# Touch_Cat_0_6.net
KiCad netlist of a schematic drawn in EAGLE
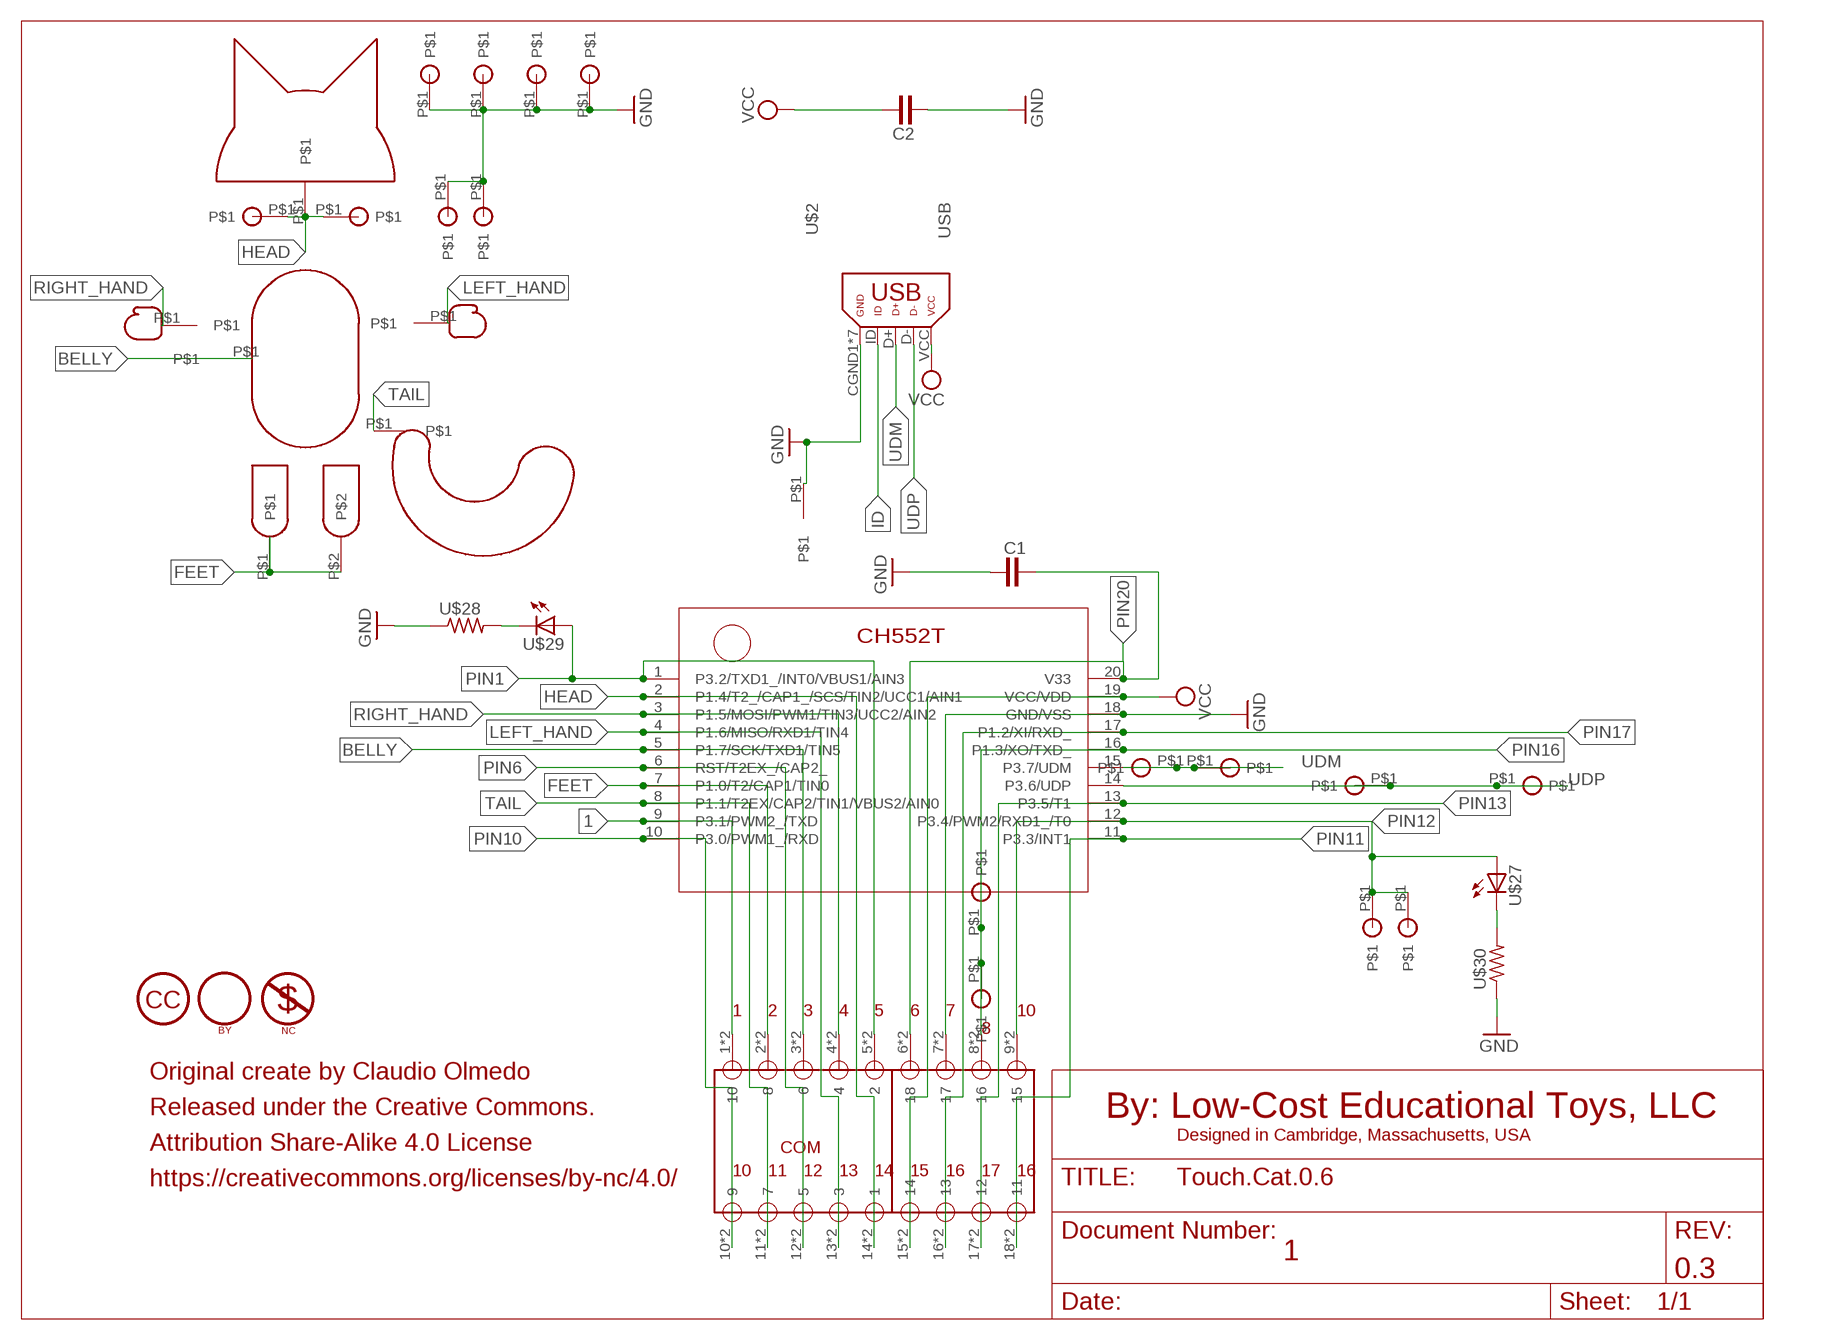
[diagram p0: schematic, sheet 1]

(export (version "E")
  (design (tool "Eeschema 10.0.6"))
  (components
    (comp (ref "C1")
      (value "CAPACITOR")
      (footprint "eagle-import:C0402")
      (libsource (lib "eagle-import") (part "CAPACITOR"))
    )
    (comp (ref "C2")
      (value "CAPACITOR")
      (footprint "eagle-import:C0402")
      (libsource (lib "eagle-import") (part "CAPACITOR"))
    )
    (comp (ref "U$1")
      (value "CHIP-TOUCH-CAT")
      (footprint "eagle-import:TSSOP20")
      (libsource (lib "eagle-import") (part "CHIP-TOUCH-CAT"))
    )
    (comp (ref "U$2")
      (value "USB")
      (footprint "eagle-import:GHI-CONNECTORS_10118192-0001LF(MICRO-USB-B-AMPHENOL-FCI)")
      (libsource (lib "eagle-import") (part "USB"))
    )
    (comp (ref "U$3")
      (value "PADVIA")
      (footprint "eagle-import:PADVIA")
      (libsource (lib "eagle-import") (part "PADVIA"))
    )
    (comp (ref "U$4")
      (value "COM-TOUCH-CAT")
      (footprint "eagle-import:COM")
      (libsource (lib "eagle-import") (part "COM-TOUCH-CAT"))
    )
    (comp (ref "U$5")
      (value "PADVIA")
      (footprint "eagle-import:PADVIA")
      (libsource (lib "eagle-import") (part "PADVIA"))
    )
    (comp (ref "U$6")
      (value "PADVIA")
      (footprint "eagle-import:PADVIA")
      (libsource (lib "eagle-import") (part "PADVIA"))
    )
    (comp (ref "U$7")
      (value "PADVIA")
      (footprint "eagle-import:PADVIA")
      (libsource (lib "eagle-import") (part "PADVIA"))
    )
    (comp (ref "U$8")
      (value "PADVIA")
      (footprint "eagle-import:PADVIA")
      (libsource (lib "eagle-import") (part "PADVIA"))
    )
    (comp (ref "U$9")
      (value "PADVIA")
      (footprint "eagle-import:PADVIA")
      (libsource (lib "eagle-import") (part "PADVIA"))
    )
    (comp (ref "U$11")
      (value "PADVIA")
      (footprint "eagle-import:PADVIA")
      (libsource (lib "eagle-import") (part "PADVIA"))
    )
    (comp (ref "U$12")
      (value "PADVIA")
      (footprint "eagle-import:PADVIA")
      (libsource (lib "eagle-import") (part "PADVIA"))
    )
    (comp (ref "U$13")
      (value "PADVIA")
      (footprint "eagle-import:PADVIA")
      (libsource (lib "eagle-import") (part "PADVIA"))
    )
    (comp (ref "U$14")
      (value "PADVIA")
      (footprint "eagle-import:PADVIA")
      (libsource (lib "eagle-import") (part "PADVIA"))
    )
    (comp (ref "U$15")
      (value "PADVIA")
      (footprint "eagle-import:PADVIA")
      (libsource (lib "eagle-import") (part "PADVIA"))
    )
    (comp (ref "U$16")
      (value "PADVIA")
      (footprint "eagle-import:PADVIA")
      (libsource (lib "eagle-import") (part "PADVIA"))
    )
    (comp (ref "U$17")
      (value "HEAD-TOUCH-CAT")
      (footprint "eagle-import:HEAD-TOUCH-CAT")
      (libsource (lib "eagle-import") (part "HEAD-TOUCH-CAT"))
    )
    (comp (ref "U$18")
      (value "BELLY-TOUCH-CAT")
      (footprint "eagle-import:BELLY-TOUCH-CAT")
      (libsource (lib "eagle-import") (part "BELLY-TOUCH-CAT"))
    )
    (comp (ref "U$19")
      (value "RIGHT_HAND-TOUCH-CAT")
      (footprint "eagle-import:RIGHT_HAND-TOUCH-CAT")
      (libsource (lib "eagle-import") (part "RIGHT_HAND-TOUCH-CAT"))
    )
    (comp (ref "U$20")
      (value "LEFT_HAND-TOUCH-CAT")
      (footprint "eagle-import:LEFT_HAND-TOUCH-CAT")
      (libsource (lib "eagle-import") (part "LEFT_HAND-TOUCH-CAT"))
    )
    (comp (ref "U$21")
      (value "FEET-TOUCH-CAT")
      (footprint "eagle-import:FEET-TOUCH-CAT")
      (libsource (lib "eagle-import") (part "FEET-TOUCH-CAT"))
    )
    (comp (ref "U$22")
      (value "TAIL-TOUCH-CAT")
      (footprint "eagle-import:TAIL-TOUCH-CAT")
      (libsource (lib "eagle-import") (part "TAIL-TOUCH-CAT"))
    )
    (comp (ref "U$23")
      (value "PADVIA")
      (footprint "eagle-import:PADVIA")
      (libsource (lib "eagle-import") (part "PADVIA"))
    )
    (comp (ref "U$24")
      (value "PADVIA")
      (footprint "eagle-import:PADVIA")
      (libsource (lib "eagle-import") (part "PADVIA"))
    )
    (comp (ref "U$25")
      (value "PADVIA")
      (footprint "eagle-import:PADVIA")
      (libsource (lib "eagle-import") (part "PADVIA"))
    )
    (comp (ref "U$26")
      (value "PADVIA")
      (footprint "eagle-import:PADVIA")
      (libsource (lib "eagle-import") (part "PADVIA"))
    )
    (comp (ref "U$27")
      (value "LED-TOUCH-CAT")
      (footprint "eagle-import:0603-ORANGE")
      (libsource (lib "eagle-import") (part "LED-TOUCH-CAT"))
    )
    (comp (ref "U$28")
      (value "RESISTOR-TOUCH-CAT")
      (footprint "eagle-import:R0402")
      (libsource (lib "eagle-import") (part "RESISTOR-TOUCH-CAT"))
    )
    (comp (ref "U$29")
      (value "LED-TOUCH-CAT")
      (footprint "eagle-import:0603-ORANGE")
      (libsource (lib "eagle-import") (part "LED-TOUCH-CAT"))
    )
    (comp (ref "U$30")
      (value "RESISTOR-TOUCH-CAT")
      (footprint "eagle-import:R0402")
      (libsource (lib "eagle-import") (part "RESISTOR-TOUCH-CAT"))
    )
    (comp (ref "U$31")
      (value "OSHW-LOGO")
      (footprint "eagle-import:OSHW-LOGO-MINI")
      (libsource (lib "eagle-import") (part "OSHW-LOGO"))
    )
    (comp (ref "U$33")
      (value "ABOUT-TOUCH-CAT")
      (footprint "eagle-import:ABOUT-TOUCH-CAT")
      (libsource (lib "eagle-import") (part "ABOUT-TOUCH-CAT"))
    )
  )
  (nets
    (net (code "1") (name "1") (class "Default")
      (node (ref "U$1") (pin "9") (pinfunction "P3.1/PWM2_/TXD_9") (pintype "bidirectional"))
      (node (ref "U$4") (pin "1") (pinfunction "10_1") (pintype "bidirectional"))
      (node (ref "U$4") (pin "1.1") (pinfunction "10_1.1") (pintype "bidirectional"))
    )
    (net (code "2") (name "BELLY") (class "Default")
      (node (ref "U$1") (pin "5") (pinfunction "P1.7/SCK/TXD1/TIN5_5") (pintype "bidirectional"))
      (node (ref "U$18") (pin "P$1") (pinfunction "P$1_P$1") (pintype "bidirectional"))
      (node (ref "U$4") (pin "3") (pinfunction "6_3") (pintype "bidirectional"))
      (node (ref "U$4") (pin "3.1") (pinfunction "6_3.1") (pintype "bidirectional"))
    )
    (net (code "3") (name "FEET") (class "Default")
      (node (ref "U$1") (pin "7") (pinfunction "P1.0/T2/CAP1/TIN0_7") (pintype "bidirectional"))
      (node (ref "U$21") (pin "P$1") (pinfunction "P$1_P$1") (pintype "bidirectional"))
      (node (ref "U$21") (pin "P$2") (pinfunction "P$2_P$2") (pintype "bidirectional"))
      (node (ref "U$4") (pin "2") (pinfunction "8_2") (pintype "bidirectional"))
      (node (ref "U$4") (pin "2.1") (pinfunction "8_2.1") (pintype "bidirectional"))
    )
    (net (code "4") (name "GND") (class "Default")
      (node (ref "C1") (pin "1") (pinfunction "1_1") (pintype "passive"))
      (node (ref "C2") (pin "1") (pinfunction "1_1") (pintype "passive"))
      (node (ref "U$1") (pin "18") (pinfunction "GND/VSS_18") (pintype "power_in"))
      (node (ref "U$2") (pin "CGND1") (pinfunction "GND_CGND1") (pintype "passive"))
      (node (ref "U$2") (pin "CGND2") (pinfunction "GND_CGND2") (pintype "passive"))
      (node (ref "U$2") (pin "CGND3") (pinfunction "GND_CGND3") (pintype "passive"))
      (node (ref "U$2") (pin "CGND4") (pinfunction "GND_CGND4") (pintype "passive"))
      (node (ref "U$2") (pin "CGND5") (pinfunction "GND_CGND5") (pintype "passive"))
      (node (ref "U$2") (pin "CGND6") (pinfunction "GND_CGND6") (pintype "passive"))
      (node (ref "U$2") (pin "GND") (pinfunction "GND_GND") (pintype "passive"))
      (node (ref "U$23") (pin "P$1") (pinfunction "P$1_P$1") (pintype "bidirectional"))
      (node (ref "U$24") (pin "P$1") (pinfunction "P$1_P$1") (pintype "bidirectional"))
      (node (ref "U$25") (pin "P$1") (pinfunction "P$1_P$1") (pintype "bidirectional"))
      (node (ref "U$26") (pin "P$1") (pinfunction "P$1_P$1") (pintype "bidirectional"))
      (node (ref "U$28") (pin "1") (pinfunction "1_1") (pintype "passive"))
      (node (ref "U$30") (pin "1") (pinfunction "1_1") (pintype "passive"))
      (node (ref "U$31") (pin "P$1") (pinfunction "P$1_P$1") (pintype "bidirectional"))
      (node (ref "U$4") (pin "7") (pinfunction "17_7") (pintype "bidirectional"))
      (node (ref "U$4") (pin "7.1") (pinfunction "17_7.1") (pintype "bidirectional"))
      (node (ref "U$6") (pin "P$1") (pinfunction "P$1_P$1") (pintype "bidirectional"))
      (node (ref "U$7") (pin "P$1") (pinfunction "P$1_P$1") (pintype "bidirectional"))
    )
    (net (code "5") (name "HEAD") (class "Default")
      (node (ref "U$1") (pin "2") (pinfunction "P1.4/T2_/CAP1_/SCS/TIN2/UCC1/AIN1_2") (pintype "bidirectional"))
      (node (ref "U$17") (pin "P$1") (pinfunction "P$1_P$1") (pintype "bidirectional"))
      (node (ref "U$4") (pin "14") (pinfunction "1_14") (pintype "bidirectional"))
      (node (ref "U$4") (pin "14.1") (pinfunction "1_14.1") (pintype "bidirectional"))
      (node (ref "U$8") (pin "P$1") (pinfunction "P$1_P$1") (pintype "bidirectional"))
      (node (ref "U$9") (pin "P$1") (pinfunction "P$1_P$1") (pintype "bidirectional"))
    )
    (net (code "6") (name "ID") (class "Default")
      (node (ref "U$2") (pin "ID") (pinfunction "ID_ID") (pintype "passive"))
    )
    (net (code "7") (name "LEFT_HAND") (class "Default")
      (node (ref "U$1") (pin "4") (pinfunction "P1.6/MISO/RXD1/TIN4_4") (pintype "bidirectional"))
      (node (ref "U$20") (pin "P$1") (pinfunction "P$1_P$1") (pintype "bidirectional"))
      (node (ref "U$4") (pin "13") (pinfunction "3_13") (pintype "bidirectional"))
      (node (ref "U$4") (pin "13.1") (pinfunction "3_13.1") (pintype "bidirectional"))
    )
    (net (code "8") (name "Net-(U$27-PadC)") (class "Default")
      (node (ref "U$27") (pin "C") (pinfunction "C_C") (pintype "passive"))
      (node (ref "U$30") (pin "2") (pinfunction "2_2") (pintype "passive"))
    )
    (net (code "9") (name "Net-(U$28-Pad2)") (class "Default")
      (node (ref "U$28") (pin "2") (pinfunction "2_2") (pintype "passive"))
      (node (ref "U$29") (pin "C") (pinfunction "C_C") (pintype "passive"))
    )
    (net (code "10") (name "PIN1") (class "Default")
      (node (ref "U$1") (pin "1") (pinfunction "P3.2/TXD1_/INT0/VBUS1/AIN3_1") (pintype "bidirectional"))
      (node (ref "U$29") (pin "A") (pinfunction "A_A") (pintype "passive"))
      (node (ref "U$4") (pin "5") (pinfunction "2_5") (pintype "bidirectional"))
      (node (ref "U$4") (pin "5.1") (pinfunction "2_5.1") (pintype "bidirectional"))
    )
    (net (code "11") (name "PIN6") (class "Default")
      (node (ref "U$1") (pin "6") (pinfunction "RST/T2EX_/CAP2__6") (pintype "bidirectional"))
      (node (ref "U$4") (pin "12") (pinfunction "5_12") (pintype "bidirectional"))
      (node (ref "U$4") (pin "12.1") (pinfunction "5_12.1") (pintype "bidirectional"))
    )
    (net (code "12") (name "PIN10") (class "Default")
      (node (ref "U$1") (pin "10") (pinfunction "P3.0/PWM1_/RXD_10") (pintype "bidirectional"))
      (node (ref "U$4") (pin "10") (pinfunction "9_10") (pintype "bidirectional"))
      (node (ref "U$4") (pin "10.1") (pinfunction "9_10.1") (pintype "bidirectional"))
    )
    (net (code "13") (name "PIN11") (class "Default")
      (node (ref "U$1") (pin "11") (pinfunction "P3.3/INT1_11") (pintype "bidirectional"))
      (node (ref "U$4") (pin "18") (pinfunction "11_18") (pintype "bidirectional"))
      (node (ref "U$4") (pin "18.1") (pinfunction "11_18.1") (pintype "bidirectional"))
    )
    (net (code "14") (name "PIN12") (class "Default")
      (node (ref "U$1") (pin "12") (pinfunction "P3.4/PWM2/RXD1_/T0_12") (pintype "bidirectional"))
      (node (ref "U$27") (pin "A") (pinfunction "A_A") (pintype "passive"))
      (node (ref "U$3") (pin "P$1") (pinfunction "P$1_P$1") (pintype "bidirectional"))
      (node (ref "U$4") (pin "9") (pinfunction "15_9") (pintype "bidirectional"))
      (node (ref "U$4") (pin "9.1") (pinfunction "15_9.1") (pintype "bidirectional"))
      (node (ref "U$5") (pin "P$1") (pinfunction "P$1_P$1") (pintype "bidirectional"))
    )
    (net (code "15") (name "PIN13") (class "Default")
      (node (ref "U$1") (pin "13") (pinfunction "P3.5/T1_13") (pintype "bidirectional"))
      (node (ref "U$4") (pin "17") (pinfunction "12_17") (pintype "bidirectional"))
      (node (ref "U$4") (pin "17.1") (pinfunction "12_17.1") (pintype "bidirectional"))
    )
    (net (code "16") (name "PIN16") (class "Default")
      (node (ref "U$1") (pin "16") (pinfunction "P1.3/XO/TXD__16") (pintype "bidirectional"))
      (node (ref "U$11") (pin "P$1") (pinfunction "P$1_P$1") (pintype "bidirectional"))
      (node (ref "U$12") (pin "P$1") (pinfunction "P$1_P$1") (pintype "bidirectional"))
      (node (ref "U$4") (pin "8") (pinfunction "16_8") (pintype "bidirectional"))
      (node (ref "U$4") (pin "8.1") (pinfunction "16_8.1") (pintype "bidirectional"))
    )
    (net (code "17") (name "PIN17") (class "Default")
      (node (ref "U$1") (pin "17") (pinfunction "P1.2/XI/RXD__17") (pintype "bidirectional"))
      (node (ref "U$4") (pin "16") (pinfunction "13_16") (pintype "bidirectional"))
      (node (ref "U$4") (pin "16.1") (pinfunction "13_16.1") (pintype "bidirectional"))
    )
    (net (code "18") (name "PIN20") (class "Default")
      (node (ref "C1") (pin "2") (pinfunction "2_2") (pintype "passive"))
      (node (ref "U$1") (pin "20") (pinfunction "V33_20") (pintype "power_in"))
      (node (ref "U$4") (pin "6") (pinfunction "18_6") (pintype "bidirectional"))
      (node (ref "U$4") (pin "6.1") (pinfunction "18_6.1") (pintype "bidirectional"))
    )
    (net (code "19") (name "RIGHT_HAND") (class "Default")
      (node (ref "U$1") (pin "3") (pinfunction "P1.5/MOSI/PWM1/TIN3/UCC2/AIN2_3") (pintype "bidirectional"))
      (node (ref "U$19") (pin "P$1") (pinfunction "P$1_P$1") (pintype "bidirectional"))
      (node (ref "U$4") (pin "4") (pinfunction "4_4") (pintype "bidirectional"))
      (node (ref "U$4") (pin "4.1") (pinfunction "4_4.1") (pintype "bidirectional"))
    )
    (net (code "20") (name "TAIL") (class "Default")
      (node (ref "U$1") (pin "8") (pinfunction "P1.1/T2EX/CAP2/TIN1/VBUS2/AIN0_8") (pintype "bidirectional"))
      (node (ref "U$22") (pin "P$1") (pinfunction "P$1_P$1") (pintype "bidirectional"))
      (node (ref "U$4") (pin "11") (pinfunction "7_11") (pintype "bidirectional"))
      (node (ref "U$4") (pin "11.1") (pinfunction "7_11.1") (pintype "bidirectional"))
    )
    (net (code "21") (name "UDM") (class "Default")
      (node (ref "U$1") (pin "15") (pinfunction "P3.7/UDM_15") (pintype "bidirectional"))
      (node (ref "U$13") (pin "P$1") (pinfunction "P$1_P$1") (pintype "bidirectional"))
      (node (ref "U$14") (pin "P$1") (pinfunction "P$1_P$1") (pintype "bidirectional"))
      (node (ref "U$2") (pin "D+") (pinfunction "D+_D+") (pintype "passive"))
    )
    (net (code "22") (name "UDP") (class "Default")
      (node (ref "U$1") (pin "14") (pinfunction "P3.6/UDP_14") (pintype "bidirectional"))
      (node (ref "U$15") (pin "P$1") (pinfunction "P$1_P$1") (pintype "bidirectional"))
      (node (ref "U$16") (pin "P$1") (pinfunction "P$1_P$1") (pintype "bidirectional"))
      (node (ref "U$2") (pin "D-") (pinfunction "D-_D-") (pintype "passive"))
    )
    (net (code "23") (name "VCC") (class "Default")
      (node (ref "C2") (pin "2") (pinfunction "2_2") (pintype "passive"))
      (node (ref "U$1") (pin "19") (pinfunction "VCC/VDD_19") (pintype "power_in"))
      (node (ref "U$2") (pin "VCC") (pinfunction "VCC_VCC") (pintype "passive"))
      (node (ref "U$4") (pin "15") (pinfunction "14_15") (pintype "bidirectional"))
      (node (ref "U$4") (pin "15.1") (pinfunction "14_15.1") (pintype "bidirectional"))
    )
  )
)
